# AT_short_bus.net
KiCad netlist of a schematic drawn in Altium Designer
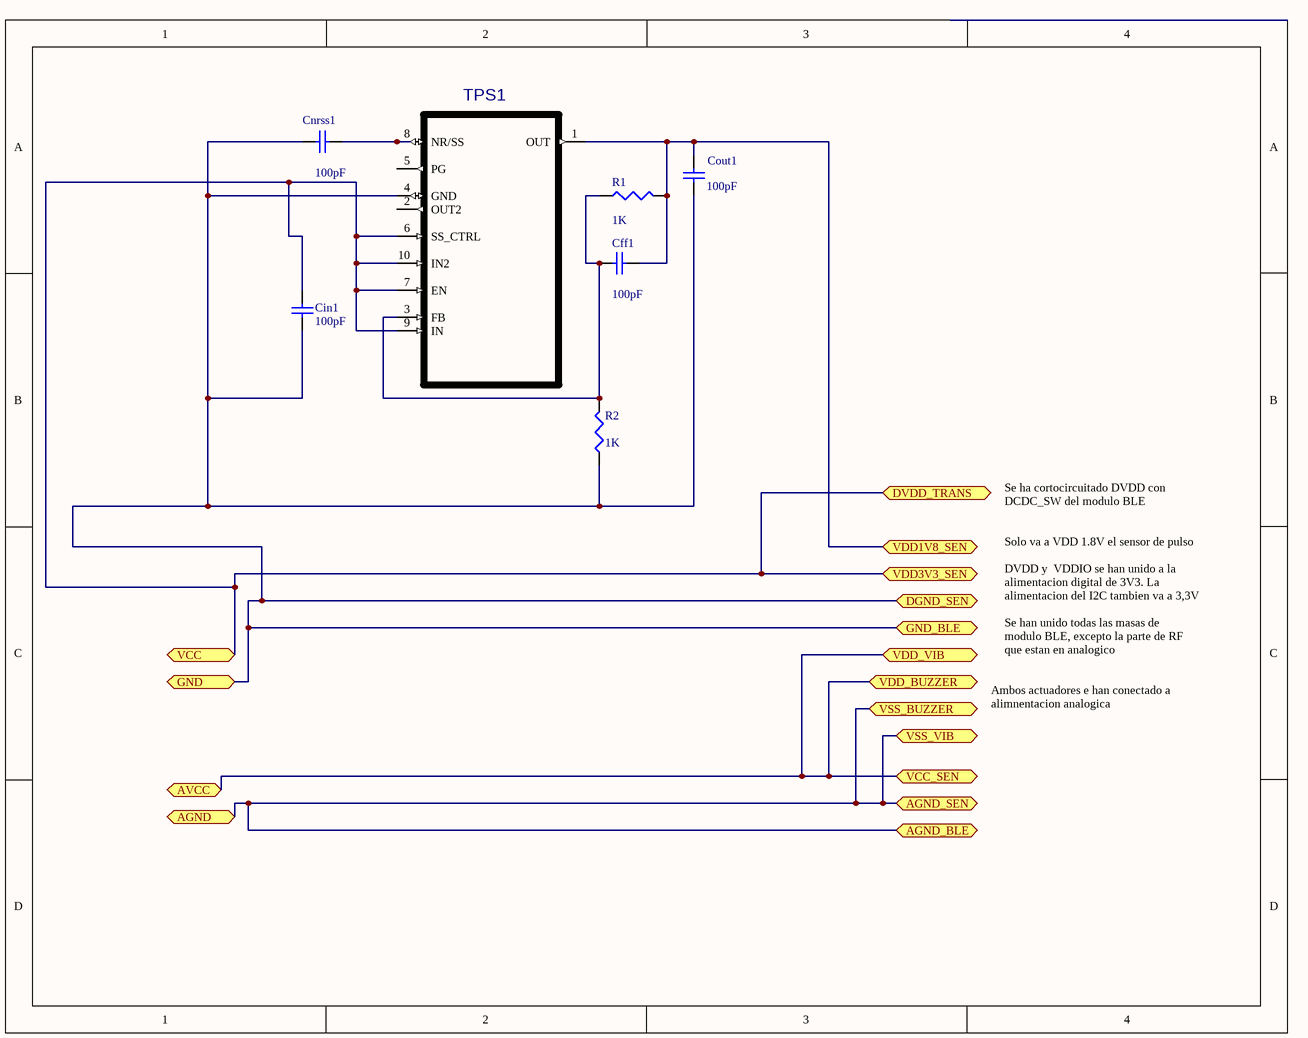
[diagram p0: AT short bus ( 7 x 4.8 inches).schdoc]

(export (version "E")
  (design (tool "Eeschema 10.0.6"))
  (components
    (comp (ref "Cff1")
      (value "100pF")
      (footprint "C1206")
      (description "Capacitor (Semiconductor SIM Model)")
      (fields (field (name "PUBLISHER") "Altium Limited"))
      (libsource (lib "Miscellaneous Devices") (part "Cap Semi"))
    )
    (comp (ref "Cin1")
      (value "100pF")
      (footprint "C1206")
      (description "Capacitor (Semiconductor SIM Model)")
      (fields (field (name "PUBLISHER") "Altium Limited"))
      (libsource (lib "Miscellaneous Devices") (part "Cap Semi"))
    )
    (comp (ref "Cnrss1")
      (value "100pF")
      (footprint "C1206")
      (description "Capacitor (Semiconductor SIM Model)")
      (fields (field (name "PUBLISHER") "Altium Limited"))
      (libsource (lib "Miscellaneous Devices") (part "Cap Semi"))
    )
    (comp (ref "Cout1")
      (value "100pF")
      (footprint "C1206")
      (description "Capacitor (Semiconductor SIM Model)")
      (fields (field (name "PUBLISHER") "Altium Limited"))
      (libsource (lib "Miscellaneous Devices") (part "Cap Semi"))
    )
    (comp (ref "R1")
      (value "1K")
      (footprint "J1-0603")
      (description "Resistor")
      (fields (field (name "PUBLISHER") "Altium Limited"))
      (libsource (lib "Miscellaneous Devices") (part "Res3"))
    )
    (comp (ref "R2")
      (value "1K")
      (footprint "J1-0603")
      (description "Resistor")
      (fields (field (name "PUBLISHER") "Altium Limited"))
      (libsource (lib "Miscellaneous Devices") (part "Res3"))
    )
    (comp (ref "TPS1")
      (value "TPS63030DSKT")
      (footprint "SON50P260X260X80-11N")
      (description "TPS7A91 (ACTIVE)  1-A, High Accuracy, Low Noise LDO Voltage Regulator")
      (fields (field (name "MF") "Texas Instruments"))
      (libsource (lib "Schematics") (part "TPS63030DSKT"))
    )
  )
  (nets
    (net (code "3") (name "/DGND_SEN") (class "Default")
      (node (ref "Cin1") (pin "1") (pinfunction "1_1") (pintype "passive"))
      (node (ref "Cnrss1") (pin "1") (pinfunction "1_1") (pintype "passive"))
      (node (ref "Cout1") (pin "1") (pinfunction "1_1") (pintype "passive"))
      (node (ref "R2") (pin "1") (pinfunction "1_1") (pintype "passive"))
      (node (ref "TPS1") (pin "4") (pinfunction "GND_4") (pintype "bidirectional"))
    )
    (net (code "4") (name "/DVDD_TRANS") (class "Default")
      (node (ref "Cin1") (pin "2") (pinfunction "2_2") (pintype "passive"))
      (node (ref "TPS1") (pin "10") (pinfunction "IN2_10") (pintype "input"))
      (node (ref "TPS1") (pin "6") (pinfunction "SS_CTRL_6") (pintype "input"))
      (node (ref "TPS1") (pin "7") (pinfunction "EN_7") (pintype "input"))
      (node (ref "TPS1") (pin "9") (pinfunction "IN_9") (pintype "input"))
    )
    (net (code "5") (name "/VDD1V8_SEN") (class "Default")
      (node (ref "Cff1") (pin "2") (pinfunction "2_2") (pintype "passive"))
      (node (ref "Cout1") (pin "2") (pinfunction "2_2") (pintype "passive"))
      (node (ref "R1") (pin "2") (pinfunction "2_2") (pintype "passive"))
      (node (ref "TPS1") (pin "1") (pinfunction "OUT_1") (pintype "output"))
    )
    (net (code "6") (name "Net-(TPS1-FB)") (class "Default")
      (node (ref "Cff1") (pin "1") (pinfunction "1_1") (pintype "passive"))
      (node (ref "R1") (pin "1") (pinfunction "1_1") (pintype "passive"))
      (node (ref "R2") (pin "2") (pinfunction "2_2") (pintype "passive"))
      (node (ref "TPS1") (pin "3") (pinfunction "FB_3") (pintype "input"))
    )
    (net (code "7") (name "Net-(TPS1-NR{slash}SS)") (class "Default")
      (node (ref "Cnrss1") (pin "2") (pinfunction "2_2") (pintype "passive"))
      (node (ref "TPS1") (pin "8") (pinfunction "NR/SS_8") (pintype "bidirectional"))
    )
    (net (code "8") (name "unconnected-(TPS1-OUT2-Pad2)") (class "Default")
      (node (ref "TPS1") (pin "2") (pinfunction "OUT2_2") (pintype "output"))
    )
    (net (code "9") (name "unconnected-(TPS1-PG-Pad5)") (class "Default")
      (node (ref "TPS1") (pin "5") (pinfunction "PG_5") (pintype "output"))
    )
    (net (code "10") (name "unconnected-(TPS1-THERMALPAD-Pad11)") (class "Default")
      (node (ref "TPS1") (pin "11") (pinfunction "THERMALPAD_11") (pintype "passive"))
    )
  )
)
